# facedancer20.net
KiCad netlist of a schematic drawn in EAGLE
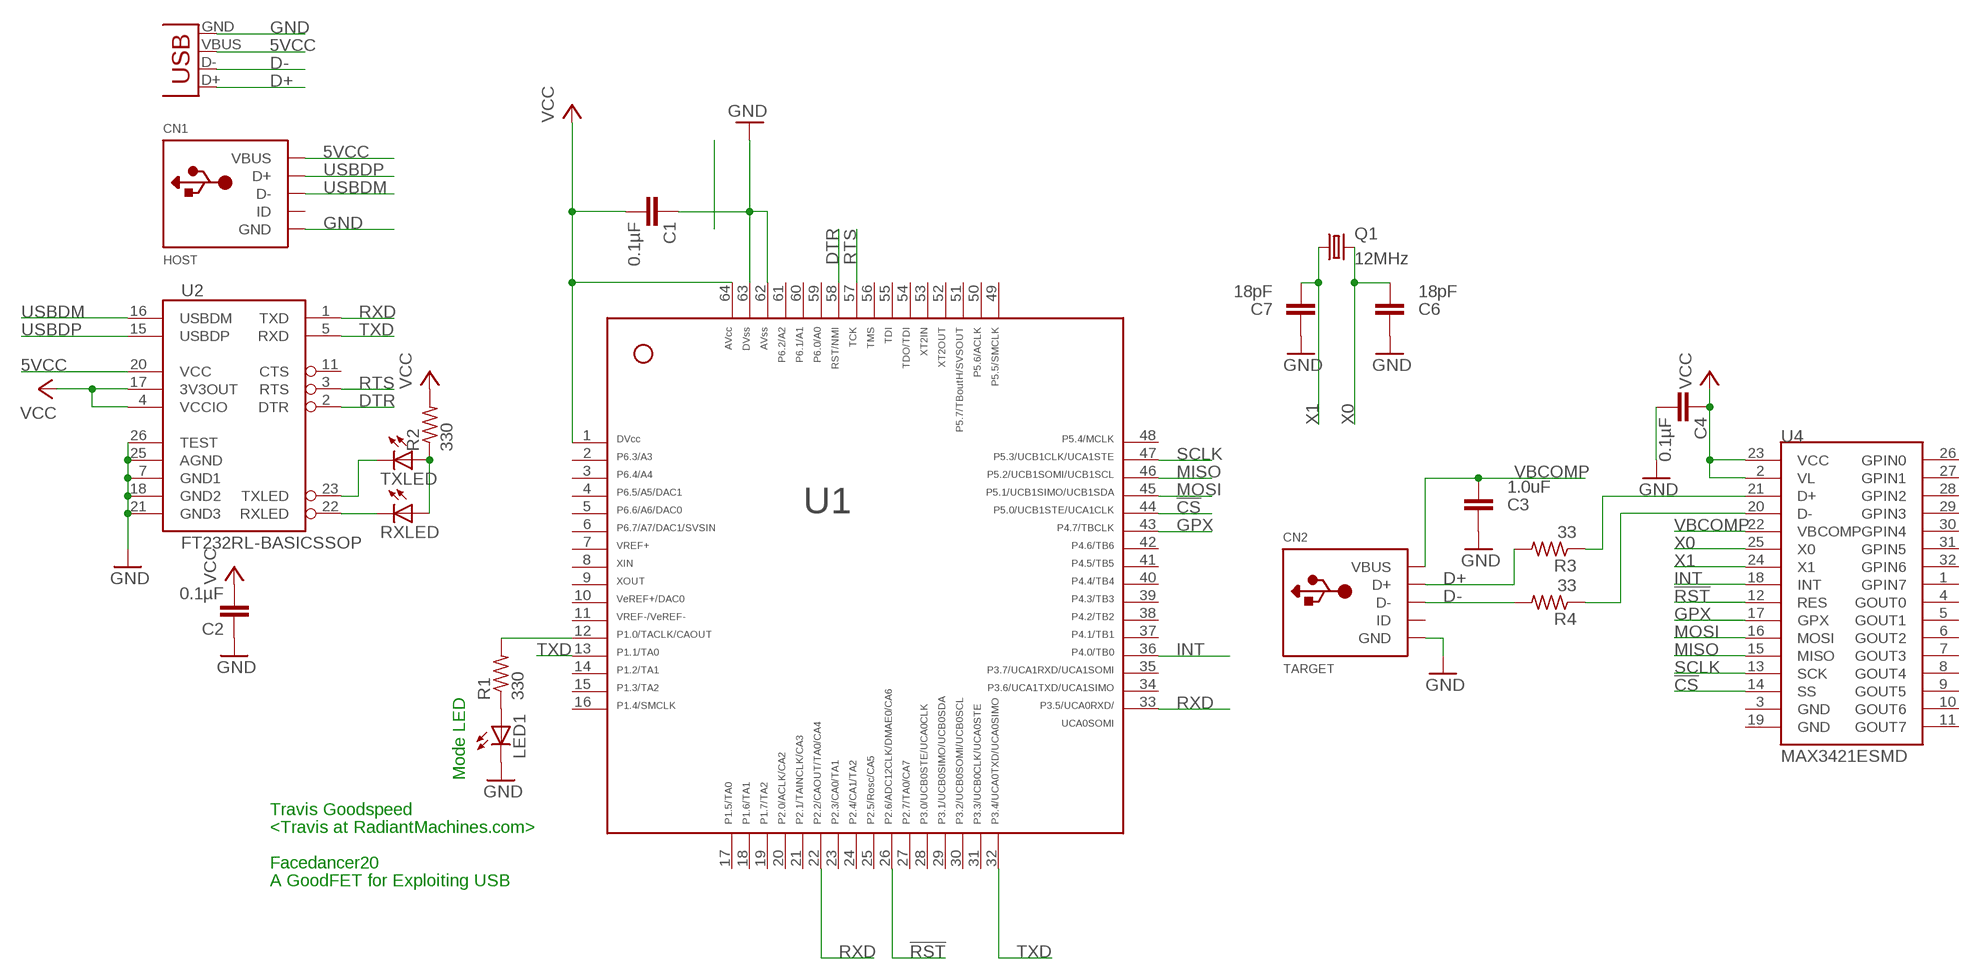
[diagram p0: schematic, sheet 1]

(export (version "E")
  (design (tool "Eeschema 10.0.6"))
  (components
    (comp (ref "C1")
      (value "0.1µF")
      (footprint "eagle-import:C0603")
      (libsource (lib "eagle-import") (part "C-EUC0603"))
    )
    (comp (ref "C2")
      (value "0.1µF")
      (footprint "eagle-import:C0603")
      (libsource (lib "eagle-import") (part "C-EUC0603"))
    )
    (comp (ref "C3")
      (value "1.0uF")
      (footprint "eagle-import:C0603")
      (libsource (lib "eagle-import") (part "C-EUC0603"))
    )
    (comp (ref "C4")
      (value "0.1µF")
      (footprint "eagle-import:C0603")
      (libsource (lib "eagle-import") (part "C-EUC0603"))
    )
    (comp (ref "C6")
      (value "18pF")
      (footprint "eagle-import:C0603")
      (libsource (lib "eagle-import") (part "C-EUC0603"))
    )
    (comp (ref "C7")
      (value "18pF")
      (footprint "eagle-import:C0603")
      (libsource (lib "eagle-import") (part "C-EUC0603"))
    )
    (comp (ref "CN1")
      (value "HOST")
      (footprint "eagle-import:USB-MINIB")
      (libsource (lib "eagle-import") (part "USBMINIB"))
    )
    (comp (ref "CN2")
      (value "TARGET")
      (footprint "eagle-import:USB-MINIB")
      (libsource (lib "eagle-import") (part "USBMINIB"))
    )
    (comp (ref "CN3")
      (value "USB-A-S")
      (footprint "eagle-import:USB-A-S")
      (libsource (lib "eagle-import") (part "USB-A-S"))
    )
    (comp (ref "LED1")
      (value "LEDCHIP-LED0603")
      (footprint "eagle-import:CHIP-LED0603")
      (libsource (lib "eagle-import") (part "LEDCHIP-LED0603"))
    )
    (comp (ref "Q1")
      (value "12MHz")
      (footprint "eagle-import:HC49UP")
      (libsource (lib "eagle-import") (part "CRYSTALHC49UP"))
    )
    (comp (ref "R1")
      (value "330")
      (footprint "eagle-import:R0603")
      (libsource (lib "eagle-import") (part "R-US_R0603"))
    )
    (comp (ref "R2")
      (value "330")
      (footprint "eagle-import:R0603")
      (libsource (lib "eagle-import") (part "R-US_R0603"))
    )
    (comp (ref "R3")
      (value "33")
      (footprint "eagle-import:R0603")
      (libsource (lib "eagle-import") (part "R-US_R0603"))
    )
    (comp (ref "R4")
      (value "33")
      (footprint "eagle-import:R0603")
      (libsource (lib "eagle-import") (part "R-US_R0603"))
    )
    (comp (ref "RXLED")
      (value "LEDCHIP-LED0603")
      (footprint "eagle-import:CHIP-LED0603")
      (libsource (lib "eagle-import") (part "LEDCHIP-LED0603"))
    )
    (comp (ref "TXLED")
      (value "LEDCHIP-LED0603")
      (footprint "eagle-import:CHIP-LED0603")
      (libsource (lib "eagle-import") (part "LEDCHIP-LED0603"))
    )
    (comp (ref "U1")
      (value "F261X---PM64")
      (footprint "eagle-import:PM_PAG64")
      (libsource (lib "eagle-import") (part "F261X---PM64"))
    )
    (comp (ref "U2")
      (value "FT232RL-BASICSSOP")
      (footprint "eagle-import:SSOP28DB")
      (libsource (lib "eagle-import") (part "FT232RL-BASICSSOP"))
    )
    (comp (ref "U4")
      (value "MAX3421ESMD")
      (footprint "eagle-import:TQFP32-5MM")
      (libsource (lib "eagle-import") (part "MAX3421ESMD"))
    )
  )
  (nets
    (net (code "1") (name "/5VCC") (class "Default")
      (node (ref "CN1") (pin "VBUS") (pinfunction "VBUS_VBUS") (pintype "power_in"))
      (node (ref "CN3") (pin "VBUS") (pinfunction "VBUS_VBUS") (pintype "bidirectional"))
      (node (ref "U2") (pin "20") (pinfunction "VCC_20") (pintype "power_in"))
    )
    (net (code "2") (name "/D+") (class "Default")
      (node (ref "CN2") (pin "D+") (pinfunction "D+_D+") (pintype "bidirectional"))
      (node (ref "CN3") (pin "D+") (pinfunction "D+_D+") (pintype "bidirectional"))
      (node (ref "R3") (pin "2") (pinfunction "2_2") (pintype "passive"))
    )
    (net (code "3") (name "/D-") (class "Default")
      (node (ref "CN2") (pin "D-") (pinfunction "D-_D-") (pintype "bidirectional"))
      (node (ref "CN3") (pin "D-") (pinfunction "D-_D-") (pintype "bidirectional"))
      (node (ref "R4") (pin "2") (pinfunction "2_2") (pintype "passive"))
    )
    (net (code "4") (name "/DTR") (class "Default")
      (node (ref "U1") (pin "58") (pinfunction "58_58") (pintype "input"))
      (node (ref "U2") (pin "2") (pinfunction "DTR_2") (pintype "bidirectional"))
    )
    (net (code "5") (name "/GPX") (class "Default")
      (node (ref "U1") (pin "43") (pinfunction "43_43") (pintype "bidirectional"))
      (node (ref "U4") (pin "17") (pinfunction "GPX_17") (pintype "bidirectional"))
    )
    (net (code "6") (name "/INT") (class "Default")
      (node (ref "U1") (pin "36") (pinfunction "36_36") (pintype "output"))
      (node (ref "U4") (pin "18") (pinfunction "INT_18") (pintype "bidirectional"))
    )
    (net (code "7") (name "/MISO") (class "Default")
      (node (ref "U1") (pin "46") (pinfunction "46_46") (pintype "bidirectional"))
      (node (ref "U4") (pin "15") (pinfunction "MISO_15") (pintype "bidirectional"))
    )
    (net (code "8") (name "/MOSI") (class "Default")
      (node (ref "U1") (pin "45") (pinfunction "45_45") (pintype "bidirectional"))
      (node (ref "U4") (pin "16") (pinfunction "MOSI_16") (pintype "bidirectional"))
    )
    (net (code "9") (name "/RTS") (class "Default")
      (node (ref "U1") (pin "57") (pinfunction "57_57") (pintype "input"))
      (node (ref "U2") (pin "3") (pinfunction "RTS_3") (pintype "bidirectional"))
    )
    (net (code "10") (name "/RXD") (class "Default")
      (node (ref "U1") (pin "22") (pinfunction "22_22") (pintype "bidirectional"))
      (node (ref "U1") (pin "33") (pinfunction "33_33") (pintype "bidirectional"))
      (node (ref "U2") (pin "1") (pinfunction "TXD_1") (pintype "output"))
    )
    (net (code "11") (name "/SCLK") (class "Default")
      (node (ref "U1") (pin "47") (pinfunction "47_47") (pintype "bidirectional"))
      (node (ref "U4") (pin "13") (pinfunction "SCK_13") (pintype "bidirectional"))
    )
    (net (code "12") (name "/TXD") (class "Default")
      (node (ref "U1") (pin "13") (pinfunction "13_13") (pintype "bidirectional"))
      (node (ref "U1") (pin "32") (pinfunction "32_32") (pintype "bidirectional"))
      (node (ref "U2") (pin "5") (pinfunction "RXD_5") (pintype "input"))
    )
    (net (code "13") (name "/USBDM") (class "Default")
      (node (ref "CN1") (pin "D-") (pinfunction "D-_D-") (pintype "bidirectional"))
      (node (ref "U2") (pin "16") (pinfunction "USBDM_16") (pintype "bidirectional"))
    )
    (net (code "14") (name "/USBDP") (class "Default")
      (node (ref "CN1") (pin "D+") (pinfunction "D+_D+") (pintype "bidirectional"))
      (node (ref "U2") (pin "15") (pinfunction "USBDP_15") (pintype "bidirectional"))
    )
    (net (code "15") (name "/VBCOMP") (class "Default")
      (node (ref "C3") (pin "2") (pinfunction "2_2") (pintype "passive"))
      (node (ref "CN2") (pin "VBUS") (pinfunction "VBUS_VBUS") (pintype "power_in"))
      (node (ref "U4") (pin "22") (pinfunction "VBCOMP_22") (pintype "bidirectional"))
    )
    (net (code "16") (name "/X0") (class "Default")
      (node (ref "C6") (pin "2") (pinfunction "2_2") (pintype "passive"))
      (node (ref "Q1") (pin "2") (pinfunction "2_2") (pintype "passive"))
      (node (ref "U4") (pin "25") (pinfunction "X0_25") (pintype "bidirectional"))
    )
    (net (code "17") (name "/X1") (class "Default")
      (node (ref "C7") (pin "2") (pinfunction "2_2") (pintype "passive"))
      (node (ref "Q1") (pin "1") (pinfunction "1_1") (pintype "passive"))
      (node (ref "U4") (pin "24") (pinfunction "X1_24") (pintype "bidirectional"))
    )
    (net (code "18") (name "/~{CS}") (class "Default")
      (node (ref "U1") (pin "44") (pinfunction "44_44") (pintype "bidirectional"))
      (node (ref "U4") (pin "14") (pinfunction "SS_14") (pintype "bidirectional"))
    )
    (net (code "19") (name "/~{RST}") (class "Default")
      (node (ref "U1") (pin "26") (pinfunction "26_26") (pintype "bidirectional"))
      (node (ref "U4") (pin "12") (pinfunction "RES_12") (pintype "bidirectional"))
    )
    (net (code "20") (name "GND") (class "Default")
      (node (ref "C1") (pin "1") (pinfunction "1_1") (pintype "passive"))
      (node (ref "C2") (pin "1") (pinfunction "1_1") (pintype "passive"))
      (node (ref "C3") (pin "1") (pinfunction "1_1") (pintype "passive"))
      (node (ref "C4") (pin "2") (pinfunction "2_2") (pintype "passive"))
      (node (ref "C6") (pin "1") (pinfunction "1_1") (pintype "passive"))
      (node (ref "C7") (pin "1") (pinfunction "1_1") (pintype "passive"))
      (node (ref "CN1") (pin "GND") (pinfunction "GND_GND") (pintype "power_in"))
      (node (ref "CN2") (pin "GND") (pinfunction "GND_GND") (pintype "power_in"))
      (node (ref "CN3") (pin "GND") (pinfunction "GND_GND") (pintype "bidirectional"))
      (node (ref "LED1") (pin "C") (pinfunction "C_C") (pintype "passive"))
      (node (ref "U1") (pin "62") (pinfunction "62_62") (pintype "power_in"))
      (node (ref "U1") (pin "63") (pinfunction "63_63") (pintype "power_in"))
      (node (ref "U2") (pin "18") (pinfunction "GND2_18") (pintype "power_in"))
      (node (ref "U2") (pin "21") (pinfunction "GND3_21") (pintype "power_in"))
      (node (ref "U2") (pin "25") (pinfunction "AGND_25") (pintype "power_in"))
      (node (ref "U2") (pin "26") (pinfunction "TEST_26") (pintype "input"))
      (node (ref "U2") (pin "7") (pinfunction "GND1_7") (pintype "power_in"))
    )
    (net (code "21") (name "Net-(LED1-PadA)") (class "Default")
      (node (ref "LED1") (pin "A") (pinfunction "A_A") (pintype "passive"))
      (node (ref "R1") (pin "1") (pinfunction "1_1") (pintype "passive"))
    )
    (net (code "22") (name "Net-(R1-Pad2)") (class "Default")
      (node (ref "R1") (pin "2") (pinfunction "2_2") (pintype "passive"))
      (node (ref "U1") (pin "12") (pinfunction "12_12") (pintype "bidirectional"))
    )
    (net (code "23") (name "Net-(R2-Pad1)") (class "Default")
      (node (ref "R2") (pin "1") (pinfunction "1_1") (pintype "passive"))
      (node (ref "RXLED") (pin "A") (pinfunction "A_A") (pintype "passive"))
      (node (ref "TXLED") (pin "A") (pinfunction "A_A") (pintype "passive"))
    )
    (net (code "24") (name "Net-(U2-RXLED)") (class "Default")
      (node (ref "RXLED") (pin "C") (pinfunction "C_C") (pintype "passive"))
      (node (ref "U2") (pin "22") (pinfunction "RXLED_22") (pintype "bidirectional"))
    )
    (net (code "25") (name "Net-(U2-TXLED)") (class "Default")
      (node (ref "TXLED") (pin "C") (pinfunction "C_C") (pintype "passive"))
      (node (ref "U2") (pin "23") (pinfunction "TXLED_23") (pintype "bidirectional"))
    )
    (net (code "26") (name "Net-(U4-D+)") (class "Default")
      (node (ref "R3") (pin "1") (pinfunction "1_1") (pintype "passive"))
      (node (ref "U4") (pin "21") (pinfunction "D+_21") (pintype "bidirectional"))
    )
    (net (code "27") (name "Net-(U4-D-)") (class "Default")
      (node (ref "R4") (pin "1") (pinfunction "1_1") (pintype "passive"))
      (node (ref "U4") (pin "20") (pinfunction "D-_20") (pintype "bidirectional"))
    )
    (net (code "28") (name "VCC") (class "Default")
      (node (ref "C1") (pin "2") (pinfunction "2_2") (pintype "passive"))
      (node (ref "C2") (pin "2") (pinfunction "2_2") (pintype "passive"))
      (node (ref "C4") (pin "1") (pinfunction "1_1") (pintype "passive"))
      (node (ref "R2") (pin "2") (pinfunction "2_2") (pintype "passive"))
      (node (ref "U1") (pin "1") (pinfunction "1_1") (pintype "power_in"))
      (node (ref "U1") (pin "64") (pinfunction "64_64") (pintype "power_in"))
      (node (ref "U2") (pin "17") (pinfunction "3V3OUT_17") (pintype "output"))
      (node (ref "U2") (pin "4") (pinfunction "VCCIO_4") (pintype "power_in"))
      (node (ref "U4") (pin "2") (pinfunction "VL_2") (pintype "bidirectional"))
      (node (ref "U4") (pin "23") (pinfunction "VCC_23") (pintype "bidirectional"))
    )
    (net (code "29") (name "unconnected-(CN1-PadID)") (class "Default")
      (node (ref "CN1") (pin "ID") (pinfunction "ID_ID") (pintype "bidirectional"))
    )
    (net (code "30") (name "unconnected-(CN2-PadID)") (class "Default")
      (node (ref "CN2") (pin "ID") (pinfunction "ID_ID") (pintype "bidirectional"))
    )
    (net (code "31") (name "unconnected-(U1-Pad2)") (class "Default")
      (node (ref "U1") (pin "2") (pinfunction "2_2") (pintype "bidirectional"))
    )
    (net (code "32") (name "unconnected-(U1-Pad3)") (class "Default")
      (node (ref "U1") (pin "3") (pinfunction "3_3") (pintype "bidirectional"))
    )
    (net (code "33") (name "unconnected-(U1-Pad4)") (class "Default")
      (node (ref "U1") (pin "4") (pinfunction "4_4") (pintype "bidirectional"))
    )
    (net (code "34") (name "unconnected-(U1-Pad5)") (class "Default")
      (node (ref "U1") (pin "5") (pinfunction "5_5") (pintype "bidirectional"))
    )
    (net (code "35") (name "unconnected-(U1-Pad6)") (class "Default")
      (node (ref "U1") (pin "6") (pinfunction "6_6") (pintype "bidirectional"))
    )
    (net (code "36") (name "unconnected-(U1-Pad7)") (class "Default")
      (node (ref "U1") (pin "7") (pinfunction "7_7") (pintype "output"))
    )
    (net (code "37") (name "unconnected-(U1-Pad8)") (class "Default")
      (node (ref "U1") (pin "8") (pinfunction "8_8") (pintype "input"))
    )
    (net (code "38") (name "unconnected-(U1-Pad9)") (class "Default")
      (node (ref "U1") (pin "9") (pinfunction "9_9") (pintype "output"))
    )
    (net (code "39") (name "unconnected-(U1-Pad10)") (class "Default")
      (node (ref "U1") (pin "10") (pinfunction "10_10") (pintype "bidirectional"))
    )
    (net (code "40") (name "unconnected-(U1-Pad11)") (class "Default")
      (node (ref "U1") (pin "11") (pinfunction "11_11") (pintype "bidirectional"))
    )
    (net (code "41") (name "unconnected-(U1-Pad14)") (class "Default")
      (node (ref "U1") (pin "14") (pinfunction "14_14") (pintype "bidirectional"))
    )
    (net (code "42") (name "unconnected-(U1-Pad15)") (class "Default")
      (node (ref "U1") (pin "15") (pinfunction "15_15") (pintype "bidirectional"))
    )
    (net (code "43") (name "unconnected-(U1-Pad16)") (class "Default")
      (node (ref "U1") (pin "16") (pinfunction "16_16") (pintype "bidirectional"))
    )
    (net (code "44") (name "unconnected-(U1-Pad17)") (class "Default")
      (node (ref "U1") (pin "17") (pinfunction "17_17") (pintype "bidirectional"))
    )
    (net (code "45") (name "unconnected-(U1-Pad18)") (class "Default")
      (node (ref "U1") (pin "18") (pinfunction "18_18") (pintype "bidirectional"))
    )
    (net (code "46") (name "unconnected-(U1-Pad19)") (class "Default")
      (node (ref "U1") (pin "19") (pinfunction "19_19") (pintype "bidirectional"))
    )
    (net (code "47") (name "unconnected-(U1-Pad20)") (class "Default")
      (node (ref "U1") (pin "20") (pinfunction "20_20") (pintype "bidirectional"))
    )
    (net (code "48") (name "unconnected-(U1-Pad21)") (class "Default")
      (node (ref "U1") (pin "21") (pinfunction "21_21") (pintype "bidirectional"))
    )
    (net (code "49") (name "unconnected-(U1-Pad23)") (class "Default")
      (node (ref "U1") (pin "23") (pinfunction "23_23") (pintype "bidirectional"))
    )
    (net (code "50") (name "unconnected-(U1-Pad24)") (class "Default")
      (node (ref "U1") (pin "24") (pinfunction "24_24") (pintype "bidirectional"))
    )
    (net (code "51") (name "unconnected-(U1-Pad25)") (class "Default")
      (node (ref "U1") (pin "25") (pinfunction "25_25") (pintype "bidirectional"))
    )
    (net (code "52") (name "unconnected-(U1-Pad27)") (class "Default")
      (node (ref "U1") (pin "27") (pinfunction "27_27") (pintype "bidirectional"))
    )
    (net (code "53") (name "unconnected-(U1-Pad28)") (class "Default")
      (node (ref "U1") (pin "28") (pinfunction "28_28") (pintype "bidirectional"))
    )
    (net (code "54") (name "unconnected-(U1-Pad29)") (class "Default")
      (node (ref "U1") (pin "29") (pinfunction "29_29") (pintype "bidirectional"))
    )
    (net (code "55") (name "unconnected-(U1-Pad30)") (class "Default")
      (node (ref "U1") (pin "30") (pinfunction "30_30") (pintype "bidirectional"))
    )
    (net (code "56") (name "unconnected-(U1-Pad31)") (class "Default")
      (node (ref "U1") (pin "31") (pinfunction "31_31") (pintype "bidirectional"))
    )
    (net (code "57") (name "unconnected-(U1-Pad34)") (class "Default")
      (node (ref "U1") (pin "34") (pinfunction "34_34") (pintype "bidirectional"))
    )
    (net (code "58") (name "unconnected-(U1-Pad35)") (class "Default")
      (node (ref "U1") (pin "35") (pinfunction "35_35") (pintype "bidirectional"))
    )
    (net (code "59") (name "unconnected-(U1-Pad37)") (class "Default")
      (node (ref "U1") (pin "37") (pinfunction "37_37") (pintype "bidirectional"))
    )
    (net (code "60") (name "unconnected-(U1-Pad38)") (class "Default")
      (node (ref "U1") (pin "38") (pinfunction "38_38") (pintype "bidirectional"))
    )
    (net (code "61") (name "unconnected-(U1-Pad39)") (class "Default")
      (node (ref "U1") (pin "39") (pinfunction "39_39") (pintype "bidirectional"))
    )
    (net (code "62") (name "unconnected-(U1-Pad40)") (class "Default")
      (node (ref "U1") (pin "40") (pinfunction "40_40") (pintype "input"))
    )
    (net (code "63") (name "unconnected-(U1-Pad41)") (class "Default")
      (node (ref "U1") (pin "41") (pinfunction "41_41") (pintype "bidirectional"))
    )
    (net (code "64") (name "unconnected-(U1-Pad42)") (class "Default")
      (node (ref "U1") (pin "42") (pinfunction "42_42") (pintype "bidirectional"))
    )
    (net (code "65") (name "unconnected-(U1-Pad48)") (class "Default")
      (node (ref "U1") (pin "48") (pinfunction "48_48") (pintype "bidirectional"))
    )
    (net (code "66") (name "unconnected-(U1-Pad49)") (class "Default")
      (node (ref "U1") (pin "49") (pinfunction "49_49") (pintype "bidirectional"))
    )
    (net (code "67") (name "unconnected-(U1-Pad50)") (class "Default")
      (node (ref "U1") (pin "50") (pinfunction "50_50") (pintype "bidirectional"))
    )
    (net (code "68") (name "unconnected-(U1-Pad51)") (class "Default")
      (node (ref "U1") (pin "51") (pinfunction "51_51") (pintype "bidirectional"))
    )
    (net (code "69") (name "unconnected-(U1-Pad52)") (class "Default")
      (node (ref "U1") (pin "52") (pinfunction "52_52") (pintype "output"))
    )
    (net (code "70") (name "unconnected-(U1-Pad53)") (class "Default")
      (node (ref "U1") (pin "53") (pinfunction "53_53") (pintype "input"))
    )
    (net (code "71") (name "unconnected-(U1-Pad54)") (class "Default")
      (node (ref "U1") (pin "54") (pinfunction "54_54") (pintype "bidirectional"))
    )
    (net (code "72") (name "unconnected-(U1-Pad55)") (class "Default")
      (node (ref "U1") (pin "55") (pinfunction "55_55") (pintype "input"))
    )
    (net (code "73") (name "unconnected-(U1-Pad56)") (class "Default")
      (node (ref "U1") (pin "56") (pinfunction "56_56") (pintype "input"))
    )
    (net (code "74") (name "unconnected-(U1-Pad59)") (class "Default")
      (node (ref "U1") (pin "59") (pinfunction "59_59") (pintype "bidirectional"))
    )
    (net (code "75") (name "unconnected-(U1-Pad60)") (class "Default")
      (node (ref "U1") (pin "60") (pinfunction "60_60") (pintype "bidirectional"))
    )
    (net (code "76") (name "unconnected-(U1-Pad61)") (class "Default")
      (node (ref "U1") (pin "61") (pinfunction "61_61") (pintype "bidirectional"))
    )
    (net (code "77") (name "unconnected-(U2-CTS-Pad11)") (class "Default")
      (node (ref "U2") (pin "11") (pinfunction "CTS_11") (pintype "bidirectional"))
    )
    (net (code "78") (name "unconnected-(U4-GND-Pad3)") (class "Default")
      (node (ref "U4") (pin "3") (pinfunction "GND_3") (pintype "bidirectional"))
    )
    (net (code "79") (name "unconnected-(U4-GND-Pad19)") (class "Default")
      (node (ref "U4") (pin "19") (pinfunction "GND_19") (pintype "bidirectional"))
    )
    (net (code "80") (name "unconnected-(U4-GOUT0-Pad4)") (class "Default")
      (node (ref "U4") (pin "4") (pinfunction "GOUT0_4") (pintype "bidirectional"))
    )
    (net (code "81") (name "unconnected-(U4-GOUT1-Pad5)") (class "Default")
      (node (ref "U4") (pin "5") (pinfunction "GOUT1_5") (pintype "bidirectional"))
    )
    (net (code "82") (name "unconnected-(U4-GOUT2-Pad6)") (class "Default")
      (node (ref "U4") (pin "6") (pinfunction "GOUT2_6") (pintype "bidirectional"))
    )
    (net (code "83") (name "unconnected-(U4-GOUT3-Pad7)") (class "Default")
      (node (ref "U4") (pin "7") (pinfunction "GOUT3_7") (pintype "bidirectional"))
    )
    (net (code "84") (name "unconnected-(U4-GOUT4-Pad8)") (class "Default")
      (node (ref "U4") (pin "8") (pinfunction "GOUT4_8") (pintype "bidirectional"))
    )
    (net (code "85") (name "unconnected-(U4-GOUT5-Pad9)") (class "Default")
      (node (ref "U4") (pin "9") (pinfunction "GOUT5_9") (pintype "bidirectional"))
    )
    (net (code "86") (name "unconnected-(U4-GOUT6-Pad10)") (class "Default")
      (node (ref "U4") (pin "10") (pinfunction "GOUT6_10") (pintype "bidirectional"))
    )
    (net (code "87") (name "unconnected-(U4-GOUT7-Pad11)") (class "Default")
      (node (ref "U4") (pin "11") (pinfunction "GOUT7_11") (pintype "bidirectional"))
    )
    (net (code "88") (name "unconnected-(U4-GPIN0-Pad26)") (class "Default")
      (node (ref "U4") (pin "26") (pinfunction "GPIN0_26") (pintype "bidirectional"))
    )
    (net (code "89") (name "unconnected-(U4-GPIN1-Pad27)") (class "Default")
      (node (ref "U4") (pin "27") (pinfunction "GPIN1_27") (pintype "bidirectional"))
    )
    (net (code "90") (name "unconnected-(U4-GPIN2-Pad28)") (class "Default")
      (node (ref "U4") (pin "28") (pinfunction "GPIN2_28") (pintype "bidirectional"))
    )
    (net (code "91") (name "unconnected-(U4-GPIN3-Pad29)") (class "Default")
      (node (ref "U4") (pin "29") (pinfunction "GPIN3_29") (pintype "bidirectional"))
    )
    (net (code "92") (name "unconnected-(U4-GPIN4-Pad30)") (class "Default")
      (node (ref "U4") (pin "30") (pinfunction "GPIN4_30") (pintype "bidirectional"))
    )
    (net (code "93") (name "unconnected-(U4-GPIN5-Pad31)") (class "Default")
      (node (ref "U4") (pin "31") (pinfunction "GPIN5_31") (pintype "bidirectional"))
    )
    (net (code "94") (name "unconnected-(U4-GPIN6-Pad32)") (class "Default")
      (node (ref "U4") (pin "32") (pinfunction "GPIN6_32") (pintype "bidirectional"))
    )
    (net (code "95") (name "unconnected-(U4-GPIN7-Pad1)") (class "Default")
      (node (ref "U4") (pin "1") (pinfunction "GPIN7_1") (pintype "bidirectional"))
    )
  )
)
